# BC95-G.net
KiCad netlist of a schematic drawn in Altium Designer
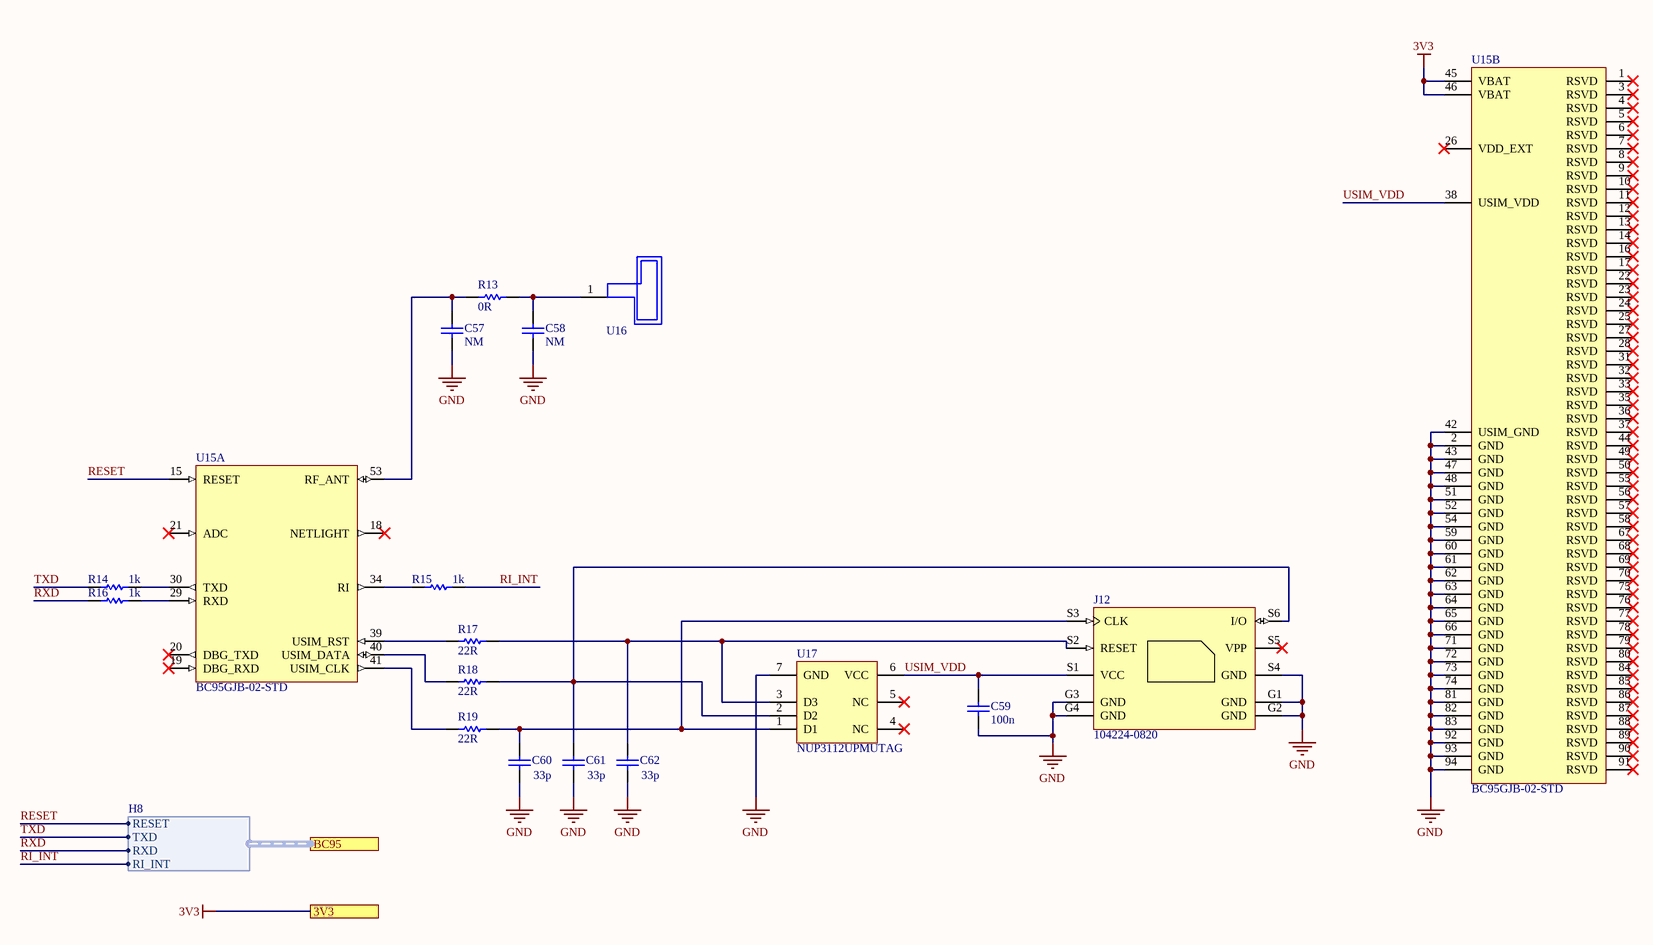
[diagram p0: BC95-G.SchDoc]

(export (version "E")
  (design (tool "Eeschema 10.0.6"))
  (components
    (comp (ref "C57")
      (value "NM")
      (footprint "CAPC1608X90X35ML10T15")
      (description "Chip Capacitor, 0.1 uF, +/- 10%, 50 V, -55 to 125 degC, 0603 (1608 Metric), RoHS, Tape and Reel")
      (fields (field (name "TOLERANCE") "10%") (field (name "VOLTAGE") "50V"))
      (libsource (lib "Altium Content Vault") (part "CAP-NP-2"))
    )
    (comp (ref "C58")
      (value "NM")
      (footprint "CAPC1608X90X35ML10T15")
      (description "Chip Capacitor, 0.1 uF, +/- 10%, 50 V, -55 to 125 degC, 0603 (1608 Metric), RoHS, Tape and Reel")
      (fields (field (name "TOLERANCE") "10%") (field (name "VOLTAGE") "50V"))
      (libsource (lib "Altium Content Vault") (part "CAP-NP-2"))
    )
    (comp (ref "C59")
      (value "100n")
      (footprint "CAPC1005X60X30ML05T10")
      (fields (field (name "MANUFACTURER") "Kemet") (field (name "PART NUMBER") "C0402C104K8PACTU"))
      (libsource (lib "Altium Content Vault") (part "CAP"))
    )
    (comp (ref "C60")
      (value "33p")
      (footprint "CAPC1005X56X25ML10T15")
      (fields
        (field (name "MANUFACTURER") "AVX Interconnect / Elco")
        (field (name "PART NUMBER") "04023A330JAT2A")
      )
      (libsource (lib "Altium Content Vault") (part "CAP"))
    )
    (comp (ref "C61")
      (value "33p")
      (footprint "CAPC1005X56X25ML10T15")
      (fields
        (field (name "MANUFACTURER") "AVX Interconnect / Elco")
        (field (name "PART NUMBER") "04023A330JAT2A")
      )
      (libsource (lib "Altium Content Vault") (part "CAP"))
    )
    (comp (ref "C62")
      (value "33p")
      (footprint "CAPC1005X56X25ML10T15")
      (fields
        (field (name "MANUFACTURER") "AVX Interconnect / Elco")
        (field (name "PART NUMBER") "04023A330JAT2A")
      )
      (libsource (lib "Altium Content Vault") (part "CAP"))
    )
    (comp (ref "J12")
      (value "104224-0820")
      (footprint "1042240820")
      (description "6 Position Card Connector NANO SIM Surface Mount, Right Angle Gold")
      (libsource (lib "ETHZ Vault") (part "1042240820"))
    )
    (comp (ref "R13")
      (value "0R")
      (footprint "RESC1609X55X30ML10T20")
      (fields (field (name "PART NUMBER") "CRCW06030000Z0EA") (field (name "MANUFACTURER") "Vishay Dale"))
      (libsource (lib "Altium Content Vault") (part "RES"))
    )
    (comp (ref "R14")
      (value "1k")
      (footprint "RESC1005X40X25NL05T05")
      (fields (field (name "MANUFACTURER") "Vishay Dale") (field (name "PART NUMBER") "CRCW04021K00FKED"))
      (libsource (lib "Altium Content Vault") (part "RES"))
    )
    (comp (ref "R15")
      (value "1k")
      (footprint "RESC1005X40X25NL05T05")
      (fields (field (name "MANUFACTURER") "Vishay Dale") (field (name "PART NUMBER") "CRCW04021K00FKED"))
      (libsource (lib "Altium Content Vault") (part "RES"))
    )
    (comp (ref "R16")
      (value "1k")
      (footprint "RESC1005X40X25NL05T05")
      (fields (field (name "MANUFACTURER") "Vishay Dale") (field (name "PART NUMBER") "CRCW04021K00FKED"))
      (libsource (lib "Altium Content Vault") (part "RES"))
    )
    (comp (ref "R17")
      (value "22R")
      (footprint "RESC1005X40X25LL05T05")
      (fields (field (name "PART NUMBER") "ERJ2RKF22R0X") (field (name "MANUFACTURER") "Panasonic"))
      (libsource (lib "Altium Content Vault") (part "RES"))
    )
    (comp (ref "R18")
      (value "22R")
      (footprint "RESC1005X40X25LL05T05")
      (fields (field (name "PART NUMBER") "ERJ2RKF22R0X") (field (name "MANUFACTURER") "Panasonic"))
      (libsource (lib "Altium Content Vault") (part "RES"))
    )
    (comp (ref "R19")
      (value "22R")
      (footprint "RESC1005X40X25LL05T05")
      (fields (field (name "PART NUMBER") "ERJ2RKF22R0X") (field (name "MANUFACTURER") "Panasonic"))
      (libsource (lib "Altium Content Vault") (part "RES"))
    )
    (comp (ref "U15")
      (value "BC95GJB-02-STD")
      (footprint "BC95GJB-02-STD")
      (description "NB-IoT Module 54Kbps UART 700MHz to 2100MHz 3.6V Surface Mount")
      (fields (field (name "MANUFACTURER") "Quectel Wireless Solutions"))
      (libsource (lib "ETHZ Vault") (part "BC95GJB-02-STD"))
    )
    (comp (ref "U16")
      (value "FR01-S4-224")
      (footprint "FR01-S4-224")
      (fields (field (name "MANUFACTURER") "Fractus Antennas S.L."))
      (libsource (lib "ETHZ Vault") (part "Antenna"))
    )
    (comp (ref "U17")
      (value "NUP3112UPMUTAG")
      (footprint "ONSC-UDFN-6-517AP-01_V")
      (fields (field (name "MANUFACTURER") "On Semiconductor"))
      (libsource (lib "Altium Content Vault") (part "ONSC-NUP311XUP_MUTAG-UDFN-6-517AP-01"))
    )
  )
  (nets
    (net (code "2") (name "/RESET") (class "Default")
      (node (ref "U15") (pin "15") (pinfunction "RESET_15") (pintype "input"))
    )
    (net (code "3") (name "/RI_INT") (class "Default")
      (node (ref "R15") (pin "2") (pinfunction "2_2") (pintype "passive"))
    )
    (net (code "4") (name "/RXD") (class "Default")
      (node (ref "R16") (pin "1") (pinfunction "1_1") (pintype "passive"))
    )
    (net (code "5") (name "/TXD") (class "Default")
      (node (ref "R14") (pin "1") (pinfunction "1_1") (pintype "passive"))
    )
    (net (code "6") (name "/USIM_VDD") (class "Default")
      (node (ref "C59") (pin "2") (pinfunction "2_2") (pintype "passive"))
      (node (ref "J12") (pin "S1") (pinfunction "VCC_S1") (pintype "power_in"))
      (node (ref "U15") (pin "38") (pinfunction "USIM_VDD_38") (pintype "power_in"))
      (node (ref "U17") (pin "6") (pinfunction "VCC_6") (pintype "power_in"))
    )
    (net (code "8") (name "3V3") (class "Default")
      (node (ref "U15") (pin "45") (pinfunction "VBAT_45") (pintype "power_in"))
      (node (ref "U15") (pin "46") (pinfunction "VBAT_46") (pintype "power_in"))
    )
    (net (code "9") (name "GND") (class "Default")
      (node (ref "C57") (pin "1") (pinfunction "1_1") (pintype "passive"))
      (node (ref "C58") (pin "1") (pinfunction "1_1") (pintype "passive"))
      (node (ref "C59") (pin "1") (pinfunction "1_1") (pintype "passive"))
      (node (ref "C60") (pin "1") (pinfunction "1_1") (pintype "passive"))
      (node (ref "C61") (pin "1") (pinfunction "1_1") (pintype "passive"))
      (node (ref "C62") (pin "1") (pinfunction "1_1") (pintype "passive"))
      (node (ref "J12") (pin "G1") (pinfunction "GND_G1") (pintype "power_in"))
      (node (ref "J12") (pin "G2") (pinfunction "GND_G2") (pintype "power_in"))
      (node (ref "J12") (pin "G3") (pinfunction "GND_G3") (pintype "power_in"))
      (node (ref "J12") (pin "G4") (pinfunction "GND_G4") (pintype "power_in"))
      (node (ref "J12") (pin "S4") (pinfunction "GND_S4") (pintype "power_in"))
      (node (ref "U15") (pin "2") (pinfunction "GND_2") (pintype "power_in"))
      (node (ref "U15") (pin "42") (pinfunction "USIM_GND_42") (pintype "power_in"))
      (node (ref "U15") (pin "43") (pinfunction "GND_43") (pintype "power_in"))
      (node (ref "U15") (pin "47") (pinfunction "GND_47") (pintype "power_in"))
      (node (ref "U15") (pin "48") (pinfunction "GND_48") (pintype "power_in"))
      (node (ref "U15") (pin "51") (pinfunction "GND_51") (pintype "power_in"))
      (node (ref "U15") (pin "52") (pinfunction "GND_52") (pintype "power_in"))
      (node (ref "U15") (pin "54") (pinfunction "GND_54") (pintype "power_in"))
      (node (ref "U15") (pin "59") (pinfunction "GND_59") (pintype "power_in"))
      (node (ref "U15") (pin "60") (pinfunction "GND_60") (pintype "power_in"))
      (node (ref "U15") (pin "61") (pinfunction "GND_61") (pintype "power_in"))
      (node (ref "U15") (pin "62") (pinfunction "GND_62") (pintype "power_in"))
      (node (ref "U15") (pin "63") (pinfunction "GND_63") (pintype "power_in"))
      (node (ref "U15") (pin "64") (pinfunction "GND_64") (pintype "power_in"))
      (node (ref "U15") (pin "65") (pinfunction "GND_65") (pintype "power_in"))
      (node (ref "U15") (pin "66") (pinfunction "GND_66") (pintype "power_in"))
      (node (ref "U15") (pin "71") (pinfunction "GND_71") (pintype "power_in"))
      (node (ref "U15") (pin "72") (pinfunction "GND_72") (pintype "power_in"))
      (node (ref "U15") (pin "73") (pinfunction "GND_73") (pintype "power_in"))
      (node (ref "U15") (pin "74") (pinfunction "GND_74") (pintype "power_in"))
      (node (ref "U15") (pin "81") (pinfunction "GND_81") (pintype "power_in"))
      (node (ref "U15") (pin "82") (pinfunction "GND_82") (pintype "power_in"))
      (node (ref "U15") (pin "83") (pinfunction "GND_83") (pintype "power_in"))
      (node (ref "U15") (pin "92") (pinfunction "GND_92") (pintype "power_in"))
      (node (ref "U15") (pin "93") (pinfunction "GND_93") (pintype "power_in"))
      (node (ref "U15") (pin "94") (pinfunction "GND_94") (pintype "power_in"))
      (node (ref "U17") (pin "7") (pinfunction "GND_7") (pintype "power_in"))
    )
    (net (code "10") (name "Net-(C58-Pad2)") (class "Default")
      (node (ref "C58") (pin "2") (pinfunction "2_2") (pintype "passive"))
      (node (ref "R13") (pin "2") (pinfunction "2_2") (pintype "passive"))
      (node (ref "U16") (pin "1") (pinfunction "1_1") (pintype "passive"))
    )
    (net (code "11") (name "Net-(J12-CLK)") (class "Default")
      (node (ref "C60") (pin "2") (pinfunction "2_2") (pintype "passive"))
      (node (ref "J12") (pin "S3") (pinfunction "CLK_S3") (pintype "input"))
      (node (ref "R19") (pin "2") (pinfunction "2_2") (pintype "passive"))
      (node (ref "U17") (pin "1") (pinfunction "D1_1") (pintype "passive"))
    )
    (net (code "12") (name "Net-(J12-I{slash}O)") (class "Default")
      (node (ref "C61") (pin "2") (pinfunction "2_2") (pintype "passive"))
      (node (ref "J12") (pin "S6") (pinfunction "I/O_S6") (pintype "bidirectional"))
      (node (ref "R18") (pin "2") (pinfunction "2_2") (pintype "passive"))
      (node (ref "U17") (pin "2") (pinfunction "D2_2") (pintype "passive"))
    )
    (net (code "13") (name "Net-(J12-RESET)") (class "Default")
      (node (ref "C62") (pin "2") (pinfunction "2_2") (pintype "passive"))
      (node (ref "J12") (pin "S2") (pinfunction "RESET_S2") (pintype "input"))
      (node (ref "R17") (pin "2") (pinfunction "2_2") (pintype "passive"))
      (node (ref "U17") (pin "3") (pinfunction "D3_3") (pintype "passive"))
    )
    (net (code "14") (name "Net-(U15A-RF_ANT)") (class "Default")
      (node (ref "C57") (pin "2") (pinfunction "2_2") (pintype "passive"))
      (node (ref "R13") (pin "1") (pinfunction "1_1") (pintype "passive"))
      (node (ref "U15") (pin "53") (pinfunction "RF_ANT_53") (pintype "bidirectional"))
    )
    (net (code "15") (name "Net-(U15A-RI)") (class "Default")
      (node (ref "R15") (pin "1") (pinfunction "1_1") (pintype "passive"))
      (node (ref "U15") (pin "34") (pinfunction "RI_34") (pintype "output"))
    )
    (net (code "16") (name "Net-(U15A-RXD)") (class "Default")
      (node (ref "R16") (pin "2") (pinfunction "2_2") (pintype "passive"))
      (node (ref "U15") (pin "29") (pinfunction "RXD_29") (pintype "input"))
    )
    (net (code "17") (name "Net-(U15A-TXD)") (class "Default")
      (node (ref "R14") (pin "2") (pinfunction "2_2") (pintype "passive"))
      (node (ref "U15") (pin "30") (pinfunction "TXD_30") (pintype "output"))
    )
    (net (code "18") (name "Net-(U15A-USIM_CLK)") (class "Default")
      (node (ref "R19") (pin "1") (pinfunction "1_1") (pintype "passive"))
      (node (ref "U15") (pin "41") (pinfunction "USIM_CLK_41") (pintype "output"))
    )
    (net (code "19") (name "Net-(U15A-USIM_DATA)") (class "Default")
      (node (ref "R18") (pin "1") (pinfunction "1_1") (pintype "passive"))
      (node (ref "U15") (pin "40") (pinfunction "USIM_DATA_40") (pintype "bidirectional"))
    )
    (net (code "20") (name "Net-(U15A-USIM_RST)") (class "Default")
      (node (ref "R17") (pin "1") (pinfunction "1_1") (pintype "passive"))
      (node (ref "U15") (pin "39") (pinfunction "USIM_RST_39") (pintype "input"))
    )
    (net (code "21") (name "unconnected-(J12-VPP-PadS5)") (class "Default")
      (node (ref "J12") (pin "S5") (pinfunction "VPP_S5") (pintype "power_in+no_connect"))
    )
    (net (code "22") (name "unconnected-(U15A-ADC-Pad21)") (class "Default")
      (node (ref "U15") (pin "21") (pinfunction "ADC_21") (pintype "input+no_connect"))
    )
    (net (code "23") (name "unconnected-(U15A-DBG_RXD-Pad19)") (class "Default")
      (node (ref "U15") (pin "19") (pinfunction "DBG_RXD_19") (pintype "input+no_connect"))
    )
    (net (code "24") (name "unconnected-(U15A-DBG_TXD-Pad20)") (class "Default")
      (node (ref "U15") (pin "20") (pinfunction "DBG_TXD_20") (pintype "output+no_connect"))
    )
    (net (code "25") (name "unconnected-(U15A-NETLIGHT-Pad18)") (class "Default")
      (node (ref "U15") (pin "18") (pinfunction "NETLIGHT_18") (pintype "output+no_connect"))
    )
    (net (code "26") (name "unconnected-(U15B-RSVD-Pad1)") (class "Default")
      (node (ref "U15") (pin "1") (pinfunction "RSVD_1") (pintype "passive+no_connect"))
    )
    (net (code "27") (name "unconnected-(U15B-RSVD-Pad3)") (class "Default")
      (node (ref "U15") (pin "3") (pinfunction "RSVD_3") (pintype "passive+no_connect"))
    )
    (net (code "28") (name "unconnected-(U15B-RSVD-Pad4)") (class "Default")
      (node (ref "U15") (pin "4") (pinfunction "RSVD_4") (pintype "passive+no_connect"))
    )
    (net (code "29") (name "unconnected-(U15B-RSVD-Pad5)") (class "Default")
      (node (ref "U15") (pin "5") (pinfunction "RSVD_5") (pintype "passive+no_connect"))
    )
    (net (code "30") (name "unconnected-(U15B-RSVD-Pad6)") (class "Default")
      (node (ref "U15") (pin "6") (pinfunction "RSVD_6") (pintype "passive+no_connect"))
    )
    (net (code "31") (name "unconnected-(U15B-RSVD-Pad7)") (class "Default")
      (node (ref "U15") (pin "7") (pinfunction "RSVD_7") (pintype "passive+no_connect"))
    )
    (net (code "32") (name "unconnected-(U15B-RSVD-Pad8)") (class "Default")
      (node (ref "U15") (pin "8") (pinfunction "RSVD_8") (pintype "passive+no_connect"))
    )
    (net (code "33") (name "unconnected-(U15B-RSVD-Pad9)") (class "Default")
      (node (ref "U15") (pin "9") (pinfunction "RSVD_9") (pintype "passive+no_connect"))
    )
    (net (code "34") (name "unconnected-(U15B-RSVD-Pad10)") (class "Default")
      (node (ref "U15") (pin "10") (pinfunction "RSVD_10") (pintype "passive+no_connect"))
    )
    (net (code "35") (name "unconnected-(U15B-RSVD-Pad11)") (class "Default")
      (node (ref "U15") (pin "11") (pinfunction "RSVD_11") (pintype "passive+no_connect"))
    )
    (net (code "36") (name "unconnected-(U15B-RSVD-Pad12)") (class "Default")
      (node (ref "U15") (pin "12") (pinfunction "RSVD_12") (pintype "passive+no_connect"))
    )
    (net (code "37") (name "unconnected-(U15B-RSVD-Pad13)") (class "Default")
      (node (ref "U15") (pin "13") (pinfunction "RSVD_13") (pintype "passive+no_connect"))
    )
    (net (code "38") (name "unconnected-(U15B-RSVD-Pad14)") (class "Default")
      (node (ref "U15") (pin "14") (pinfunction "RSVD_14") (pintype "passive+no_connect"))
    )
    (net (code "39") (name "unconnected-(U15B-RSVD-Pad16)") (class "Default")
      (node (ref "U15") (pin "16") (pinfunction "RSVD_16") (pintype "passive+no_connect"))
    )
    (net (code "40") (name "unconnected-(U15B-RSVD-Pad17)") (class "Default")
      (node (ref "U15") (pin "17") (pinfunction "RSVD_17") (pintype "passive+no_connect"))
    )
    (net (code "41") (name "unconnected-(U15B-RSVD-Pad22)") (class "Default")
      (node (ref "U15") (pin "22") (pinfunction "RSVD_22") (pintype "passive+no_connect"))
    )
    (net (code "42") (name "unconnected-(U15B-RSVD-Pad23)") (class "Default")
      (node (ref "U15") (pin "23") (pinfunction "RSVD_23") (pintype "passive+no_connect"))
    )
    (net (code "43") (name "unconnected-(U15B-RSVD-Pad24)") (class "Default")
      (node (ref "U15") (pin "24") (pinfunction "RSVD_24") (pintype "passive+no_connect"))
    )
    (net (code "44") (name "unconnected-(U15B-RSVD-Pad25)") (class "Default")
      (node (ref "U15") (pin "25") (pinfunction "RSVD_25") (pintype "passive+no_connect"))
    )
    (net (code "45") (name "unconnected-(U15B-RSVD-Pad27)") (class "Default")
      (node (ref "U15") (pin "27") (pinfunction "RSVD_27") (pintype "passive+no_connect"))
    )
    (net (code "46") (name "unconnected-(U15B-RSVD-Pad28)") (class "Default")
      (node (ref "U15") (pin "28") (pinfunction "RSVD_28") (pintype "passive+no_connect"))
    )
    (net (code "47") (name "unconnected-(U15B-RSVD-Pad31)") (class "Default")
      (node (ref "U15") (pin "31") (pinfunction "RSVD_31") (pintype "passive+no_connect"))
    )
    (net (code "48") (name "unconnected-(U15B-RSVD-Pad32)") (class "Default")
      (node (ref "U15") (pin "32") (pinfunction "RSVD_32") (pintype "passive+no_connect"))
    )
    (net (code "49") (name "unconnected-(U15B-RSVD-Pad33)") (class "Default")
      (node (ref "U15") (pin "33") (pinfunction "RSVD_33") (pintype "passive+no_connect"))
    )
    (net (code "50") (name "unconnected-(U15B-RSVD-Pad35)") (class "Default")
      (node (ref "U15") (pin "35") (pinfunction "RSVD_35") (pintype "passive+no_connect"))
    )
    (net (code "51") (name "unconnected-(U15B-RSVD-Pad36)") (class "Default")
      (node (ref "U15") (pin "36") (pinfunction "RSVD_36") (pintype "passive+no_connect"))
    )
    (net (code "52") (name "unconnected-(U15B-RSVD-Pad37)") (class "Default")
      (node (ref "U15") (pin "37") (pinfunction "RSVD_37") (pintype "passive+no_connect"))
    )
    (net (code "53") (name "unconnected-(U15B-RSVD-Pad44)") (class "Default")
      (node (ref "U15") (pin "44") (pinfunction "RSVD_44") (pintype "passive+no_connect"))
    )
    (net (code "54") (name "unconnected-(U15B-RSVD-Pad49)") (class "Default")
      (node (ref "U15") (pin "49") (pinfunction "RSVD_49") (pintype "passive+no_connect"))
    )
    (net (code "55") (name "unconnected-(U15B-RSVD-Pad50)") (class "Default")
      (node (ref "U15") (pin "50") (pinfunction "RSVD_50") (pintype "passive+no_connect"))
    )
    (net (code "56") (name "unconnected-(U15B-RSVD-Pad55)") (class "Default")
      (node (ref "U15") (pin "55") (pinfunction "RSVD_55") (pintype "passive+no_connect"))
    )
    (net (code "57") (name "unconnected-(U15B-RSVD-Pad56)") (class "Default")
      (node (ref "U15") (pin "56") (pinfunction "RSVD_56") (pintype "passive+no_connect"))
    )
    (net (code "58") (name "unconnected-(U15B-RSVD-Pad57)") (class "Default")
      (node (ref "U15") (pin "57") (pinfunction "RSVD_57") (pintype "passive+no_connect"))
    )
    (net (code "59") (name "unconnected-(U15B-RSVD-Pad58)") (class "Default")
      (node (ref "U15") (pin "58") (pinfunction "RSVD_58") (pintype "passive+no_connect"))
    )
    (net (code "60") (name "unconnected-(U15B-RSVD-Pad67)") (class "Default")
      (node (ref "U15") (pin "67") (pinfunction "RSVD_67") (pintype "passive+no_connect"))
    )
    (net (code "61") (name "unconnected-(U15B-RSVD-Pad68)") (class "Default")
      (node (ref "U15") (pin "68") (pinfunction "RSVD_68") (pintype "passive+no_connect"))
    )
    (net (code "62") (name "unconnected-(U15B-RSVD-Pad69)") (class "Default")
      (node (ref "U15") (pin "69") (pinfunction "RSVD_69") (pintype "passive+no_connect"))
    )
    (net (code "63") (name "unconnected-(U15B-RSVD-Pad70)") (class "Default")
      (node (ref "U15") (pin "70") (pinfunction "RSVD_70") (pintype "passive+no_connect"))
    )
    (net (code "64") (name "unconnected-(U15B-RSVD-Pad75)") (class "Default")
      (node (ref "U15") (pin "75") (pinfunction "RSVD_75") (pintype "passive+no_connect"))
    )
    (net (code "65") (name "unconnected-(U15B-RSVD-Pad76)") (class "Default")
      (node (ref "U15") (pin "76") (pinfunction "RSVD_76") (pintype "passive+no_connect"))
    )
    (net (code "66") (name "unconnected-(U15B-RSVD-Pad77)") (class "Default")
      (node (ref "U15") (pin "77") (pinfunction "RSVD_77") (pintype "passive+no_connect"))
    )
    (net (code "67") (name "unconnected-(U15B-RSVD-Pad78)") (class "Default")
      (node (ref "U15") (pin "78") (pinfunction "RSVD_78") (pintype "passive+no_connect"))
    )
    (net (code "68") (name "unconnected-(U15B-RSVD-Pad79)") (class "Default")
      (node (ref "U15") (pin "79") (pinfunction "RSVD_79") (pintype "passive+no_connect"))
    )
    (net (code "69") (name "unconnected-(U15B-RSVD-Pad80)") (class "Default")
      (node (ref "U15") (pin "80") (pinfunction "RSVD_80") (pintype "passive+no_connect"))
    )
    (net (code "70") (name "unconnected-(U15B-RSVD-Pad84)") (class "Default")
      (node (ref "U15") (pin "84") (pinfunction "RSVD_84") (pintype "passive+no_connect"))
    )
    (net (code "71") (name "unconnected-(U15B-RSVD-Pad85)") (class "Default")
      (node (ref "U15") (pin "85") (pinfunction "RSVD_85") (pintype "passive+no_connect"))
    )
    (net (code "72") (name "unconnected-(U15B-RSVD-Pad86)") (class "Default")
      (node (ref "U15") (pin "86") (pinfunction "RSVD_86") (pintype "passive+no_connect"))
    )
    (net (code "73") (name "unconnected-(U15B-RSVD-Pad87)") (class "Default")
      (node (ref "U15") (pin "87") (pinfunction "RSVD_87") (pintype "passive+no_connect"))
    )
    (net (code "74") (name "unconnected-(U15B-RSVD-Pad88)") (class "Default")
      (node (ref "U15") (pin "88") (pinfunction "RSVD_88") (pintype "passive+no_connect"))
    )
    (net (code "75") (name "unconnected-(U15B-RSVD-Pad89)") (class "Default")
      (node (ref "U15") (pin "89") (pinfunction "RSVD_89") (pintype "passive+no_connect"))
    )
    (net (code "76") (name "unconnected-(U15B-RSVD-Pad90)") (class "Default")
      (node (ref "U15") (pin "90") (pinfunction "RSVD_90") (pintype "passive+no_connect"))
    )
    (net (code "77") (name "unconnected-(U15B-RSVD-Pad91)") (class "Default")
      (node (ref "U15") (pin "91") (pinfunction "RSVD_91") (pintype "passive+no_connect"))
    )
    (net (code "78") (name "unconnected-(U15B-VDD_EXT-Pad26)") (class "Default")
      (node (ref "U15") (pin "26") (pinfunction "VDD_EXT_26") (pintype "power_in+no_connect"))
    )
    (net (code "79") (name "unconnected-(U17-NC-Pad4)") (class "Default")
      (node (ref "U17") (pin "4") (pinfunction "NC_4") (pintype "passive+no_connect"))
    )
    (net (code "80") (name "unconnected-(U17-NC-Pad5)") (class "Default")
      (node (ref "U17") (pin "5") (pinfunction "NC_5") (pintype "passive+no_connect"))
    )
  )
)
